# ExtensionBoard.net
KiCad netlist of a schematic drawn in Altium Designer
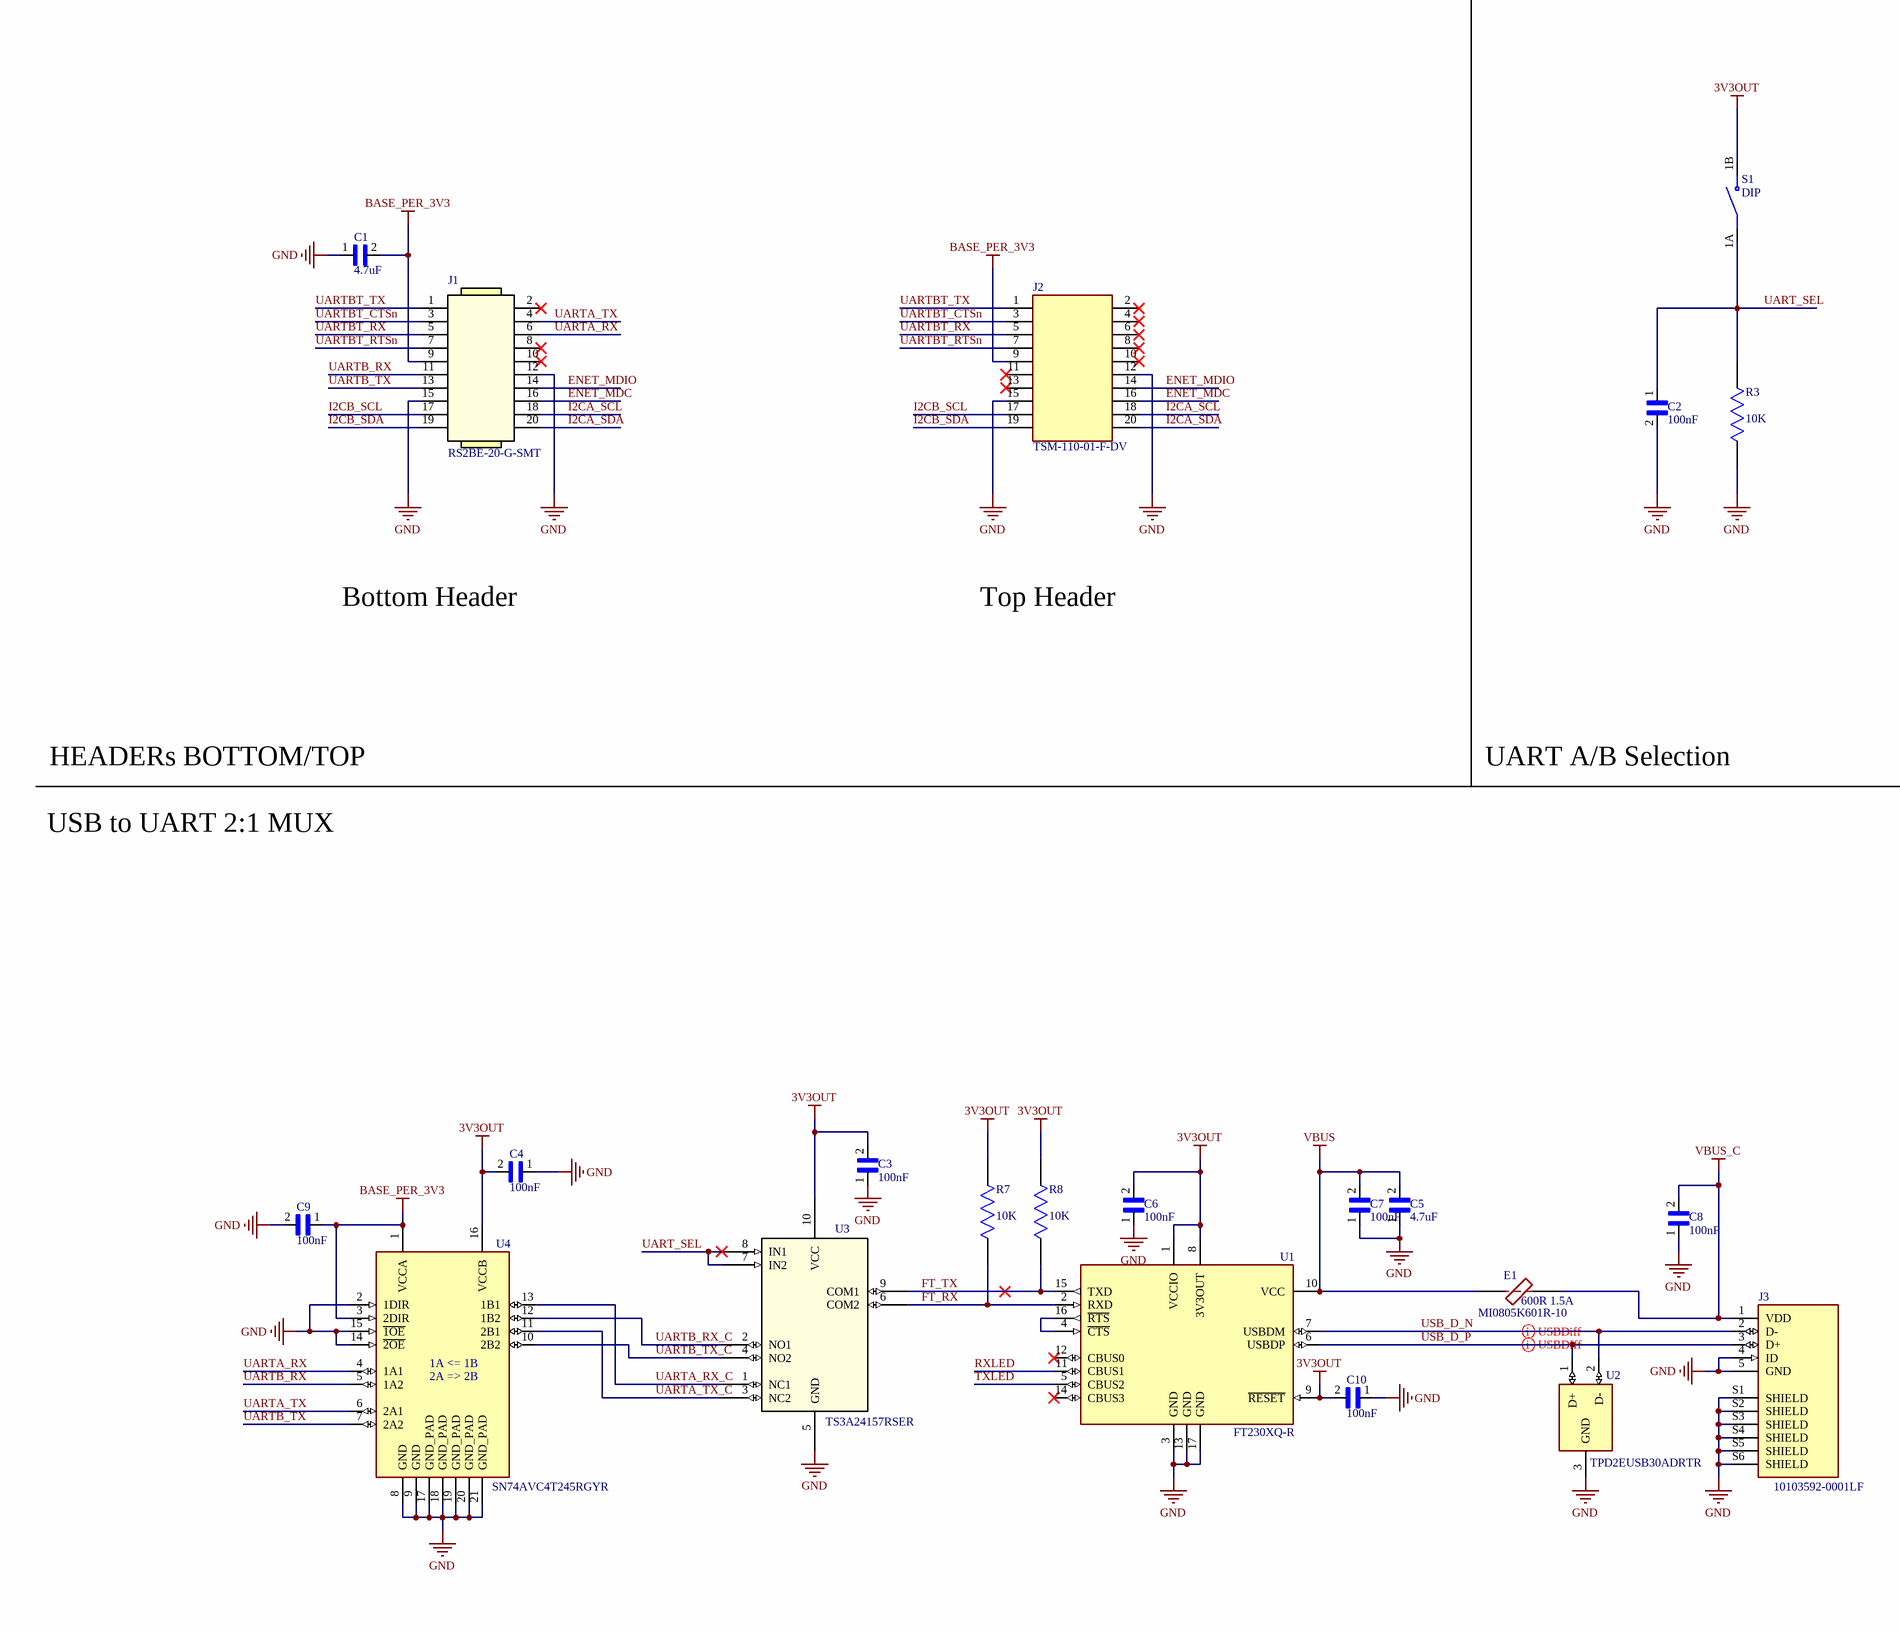
[diagram p0: ExtensionBoard.SchDoc, left]
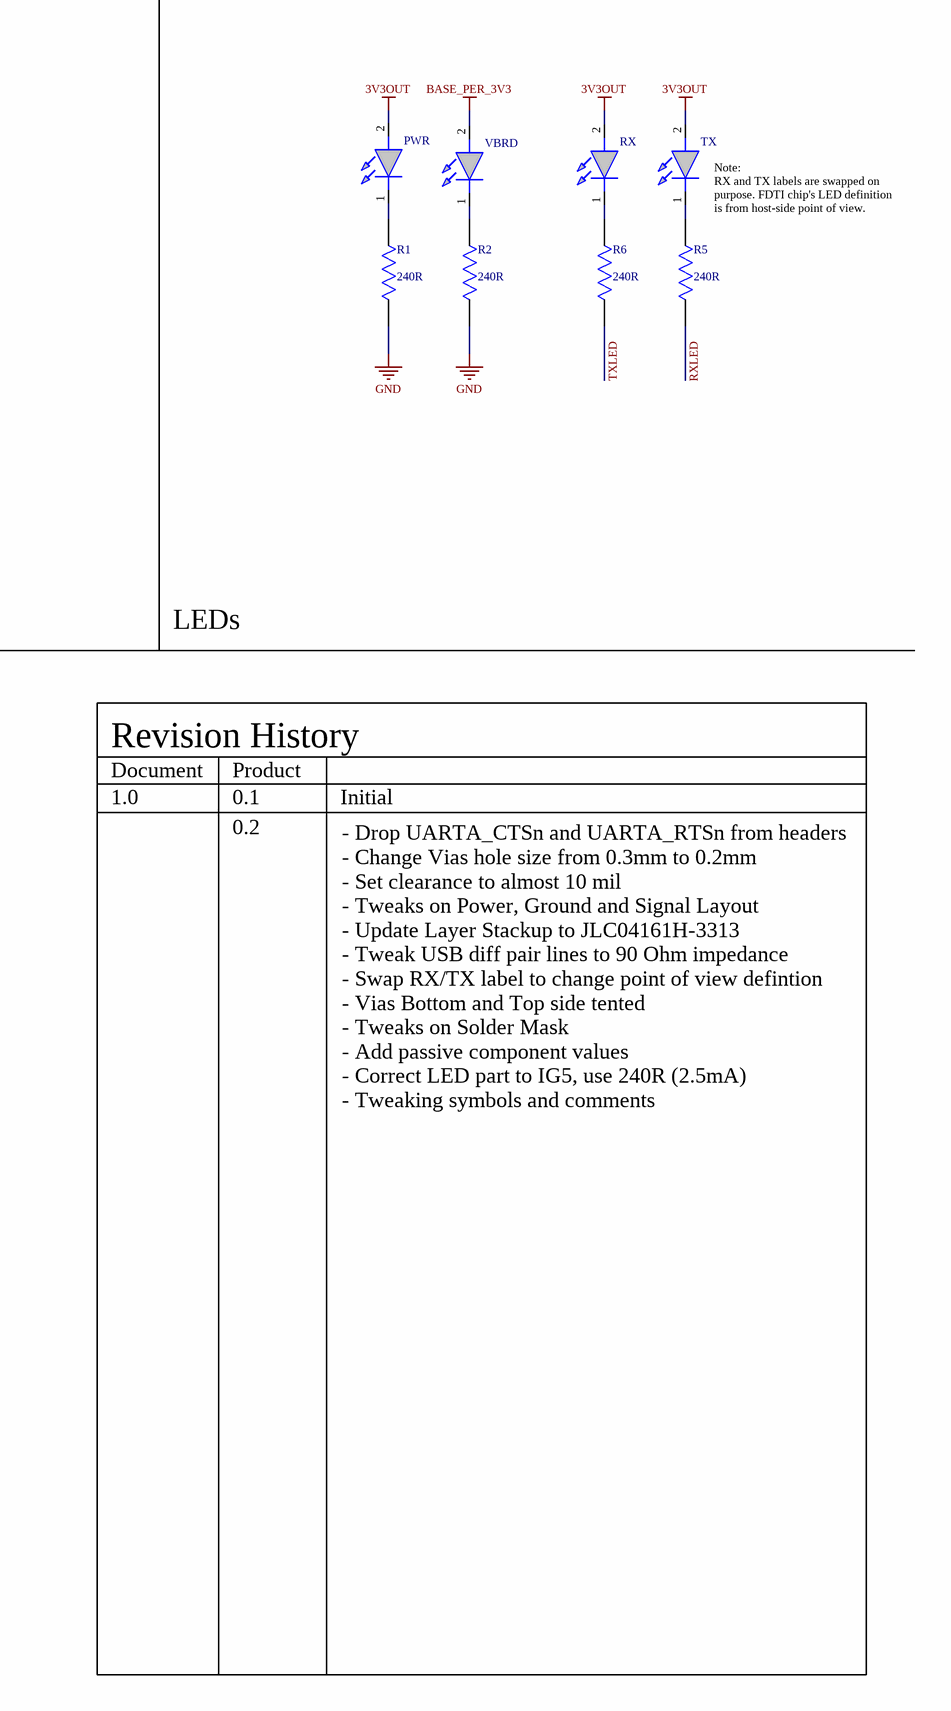
[diagram p1: ExtensionBoard.SchDoc, right]

(export (version "E")
  (design (tool "Eeschema 10.0.6"))
  (components
    (comp (ref "C1")
      (value "4.7uF")
      (footprint "CAPC1608X90N")
      (description "CAPACITOR, MLCC, X5R, 4.7UF, 10V, 0603, REEL, FULL REEL")
      (fields (field (name "MP") "LMK107BJ475KAHT"))
      (libsource (lib "LMK107BJ475KAHT") (part "LMK107BJ475KAHT"))
    )
    (comp (ref "C2")
      (value "100nF")
      (footprint "CAPC1608X90N")
      (description "Cap Ceramic 0.1uF 16V X7R 10% SMD 0603 125ÂÂŽ Paper T/R")
      (fields (field (name "MP") "0603YC104K4T4A"))
      (libsource (lib "0603YC104K4T4A") (part "0603YC104K4T4A"))
    )
    (comp (ref "C3")
      (value "100nF")
      (footprint "CAPC1608X90N")
      (description "Cap Ceramic 0.1uF 16V X7R 10% SMD 0603 125ÂÂŽ Paper T/R")
      (fields (field (name "MP") "0603YC104K4T4A"))
      (libsource (lib "") (part "0603YC104K4T4A_2"))
    )
    (comp (ref "C4")
      (value "100nF")
      (footprint "CAPC1608X90N")
      (description "Cap Ceramic 0.1uF 16V X7R 10% SMD 0603 125ÂÂŽ Paper T/R")
      (fields (field (name "MP") "0603YC104K4T4A"))
      (libsource (lib "") (part "0603YC104K4T4A_1"))
    )
    (comp (ref "C5")
      (value "4.7uF")
      (footprint "CAPC1608X90N")
      (description "CAPACITOR, MLCC, X5R, 4.7UF, 10V, 0603, REEL, FULL REEL")
      (fields (field (name "MP") "LMK107BJ475KAHT"))
      (libsource (lib "") (part "LMK107BJ475KAHT_1"))
    )
    (comp (ref "C6")
      (value "100nF")
      (footprint "CAPC1608X90N")
      (description "Cap Ceramic 0.1uF 16V X7R 10% SMD 0603 125ÂÂŽ Paper T/R")
      (fields (field (name "MP") "0603YC104K4T4A"))
      (libsource (lib "") (part "0603YC104K4T4A_2"))
    )
    (comp (ref "C7")
      (value "100nF")
      (footprint "CAPC1608X90N")
      (description "Cap Ceramic 0.1uF 16V X7R 10% SMD 0603 125ÂÂŽ Paper T/R")
      (fields (field (name "MP") "0603YC104K4T4A"))
      (libsource (lib "") (part "0603YC104K4T4A_2"))
    )
    (comp (ref "C8")
      (value "100nF")
      (footprint "CAPC1608X90N")
      (description "Cap Ceramic 0.1uF 16V X7R 10% SMD 0603 125ÂÂŽ Paper T/R")
      (fields (field (name "MP") "0603YC104K4T4A"))
      (libsource (lib "") (part "0603YC104K4T4A_2"))
    )
    (comp (ref "C9")
      (value "100nF")
      (footprint "CAPC1608X90N")
      (description "Cap Ceramic 0.1uF 16V X7R 10% SMD 0603 125ÂÂŽ Paper T/R")
      (fields (field (name "MP") "0603YC104K4T4A"))
      (libsource (lib "") (part "0603YC104K4T4A_1"))
    )
    (comp (ref "C10")
      (value "100nF")
      (footprint "CAPC1608X90N")
      (description "Cap Ceramic 0.1uF 16V X7R 10% SMD 0603 125ÂÂŽ Paper T/R")
      (fields (field (name "MP") "0603YC104K4T4A"))
      (libsource (lib "") (part "0603YC104K4T4A_1"))
    )
    (comp (ref "E1")
      (value "MI0805K601R-10")
      (footprint "FB_MI0805K601R-10")
      (description "600 Ohms @ 100MHz 1 Power Line Ferrite Bead 0805 (2012 Metric) 1.5A 100mOhm")
      (fields (field (name "ALTIUM_VALUE") "600R 1.5A") (field (name "MF") "Laird-Signal Integrity"))
      (libsource (lib "MI0805K601R-10") (part "MI0805K601R-10"))
    )
    (comp (ref "J1")
      (value "RS2BE-20-G-SMT")
      (footprint "CONN_RS2BE-20-G-SMT_ADM")
      (description "No Description Available")
      (libsource (lib "RS2BE-20-G-SMT") (part "RS2BE-20-G-SMT"))
    )
    (comp (ref "J2")
      (value "TSM-110-01-F-DV")
      (footprint "SAMTEC_TSM-110-01-F-DV")
      (fields (field (name "MF") "Samtec"))
      (libsource (lib "TSM-110-01-F-DV") (part "TSM-110-01-F-DV"))
    )
    (comp (ref "J3")
      (value "10103592-0001LF")
      (footprint "AMPHENOL_10103592-0001LF")
      (description "Micro USB 2.0, Input Output Connectors, B TYPE REVERSE")
      (fields (field (name "MF") "Amphenol ICC") (field (name "DIGI-KEY_PART_NUMBER") "609-4048-2-ND"))
      (libsource (lib "10103592-0001LF") (part "10103592-0001LF"))
    )
    (comp (ref "PWR")
      (value "QBL595-IG5")
      (footprint "LED 0402_1005 GREEN")
      (description "LED Green Clear 0402 SMD")
      (libsource (lib "QBLP595-IG5") (part "QBL595-IG5"))
    )
    (comp (ref "R1")
      (value "240R")
      (footprint "RESC1508X55N")
      (fields (field (name "MP") "RMCF0603JT10K0") (field (name "Comment") "RMCF0603JT240R"))
      (libsource (lib "RMCF0603JT10K0") (part "RMCF0603JT10K0"))
    )
    (comp (ref "R2")
      (value "240R")
      (footprint "RESC1508X55N")
      (fields (field (name "MP") "RMCF0603JT10K0") (field (name "Comment") "RMCF0603JT240R"))
      (libsource (lib "RMCF0603JT10K0") (part "RMCF0603JT10K0"))
    )
    (comp (ref "R3")
      (value "10K")
      (footprint "RESC1508X55N")
      (fields (field (name "MP") "RMCF0603JT10K0"))
      (libsource (lib "RMCF0603JT10K0") (part "RMCF0603JT10K0"))
    )
    (comp (ref "R5")
      (value "240R")
      (footprint "RESC1508X55N")
      (fields (field (name "MP") "RMCF0603JT10K0") (field (name "Comment") "RMCF0603JT240R"))
      (libsource (lib "RMCF0603JT10K0") (part "RMCF0603JT10K0"))
    )
    (comp (ref "R6")
      (value "240R")
      (footprint "RESC1508X55N")
      (fields (field (name "MP") "RMCF0603JT10K0") (field (name "Comment") "RMCF0603JT240R"))
      (libsource (lib "RMCF0603JT10K0") (part "RMCF0603JT10K0"))
    )
    (comp (ref "R7")
      (value "10K")
      (footprint "RESC1508X55N")
      (fields (field (name "MP") "RMCF0603JT10K0"))
      (libsource (lib "RMCF0603JT10K0") (part "RMCF0603JT10K0"))
    )
    (comp (ref "R8")
      (value "10K")
      (footprint "RESC1508X55N")
      (fields (field (name "MP") "RMCF0603JT10K0"))
      (libsource (lib "RMCF0603JT10K0") (part "RMCF0603JT10K0"))
    )
    (comp (ref "RX")
      (value "QBL595-IG5")
      (footprint "LED 0402_1005 GREEN")
      (description "LED Green Clear 0402 SMD")
      (libsource (lib "QBLP595-IG5") (part "QBL595-IG5"))
    )
    (comp (ref "S1")
      (value "DIP")
      (footprint "SW_DS04-254-2-01BK-SMT")
      (description "1 Position, Surface Mount, 2.54 mm Pitch, Flat Slide Actuator, Flat Bottom, SMT Pin, DIP Switch")
      (fields (field (name "MP") "DS04-254-2-01BK-SMT") (field (name "MF") "CUI Devices"))
      (libsource (lib "DS04-254-2-01BK-SMT") (part "DS04-254-2-01BK-SMT"))
    )
    (comp (ref "TX")
      (value "QBL595-IG5")
      (footprint "LED 0402_1005 GREEN")
      (description "LED Green Clear 0402 SMD")
      (libsource (lib "QBLP595-IG5") (part "QBL595-IG5"))
    )
    (comp (ref "U1")
      (value "FT230XQ-R")
      (footprint "FT230XQ-R:QFN65P400X400X80-17N")
      (description "USB Bridge, USB to UART USB 2.0 UART Interface 16-QFN (4x4)")
      (fields (field (name "MF") "FTDI,"))
      (libsource (lib "FT230XQ-R") (part "FT230XQ-R"))
    )
    (comp (ref "U2")
      (value "TPD2EUSB30ADRTR")
      (footprint "SOTFL35P100X50-3N")
      (description "2-Channel ESD/Surge Solution for High-Speed Low-Voltage Interface")
      (fields (field (name "MF") "Texas Instruments"))
      (libsource (lib "TPD2EUSB30ADRTR") (part "TPD2EUSB30ADRTR"))
    )
    (comp (ref "U3")
      (value "TS3A24157RSER")
      (footprint "RSE10")
      (description "No Description Available")
      (libsource (lib "TS3A24157RSER") (part "TS3A24157RSER"))
    )
    (comp (ref "U4")
      (value "SN74AVC4T245RGYR")
      (footprint "QFN50P400X350X100-17N:QFN50P400X350X100-17N")
      (libsource (lib "SN74AVC4T245RGYR") (part "SN74AVC4T245RGYR"))
    )
    (comp (ref "VBRD")
      (value "QBL595-IG5")
      (footprint "LED 0402_1005 GREEN")
      (description "LED Green Clear 0402 SMD")
      (libsource (lib "QBLP595-IG5") (part "QBL595-IG5"))
    )
  )
  (nets
    (net (code "1") (name "/ENET_MDC") (class "Default")
      (node (ref "J1") (pin "16") (pinfunction "16_16") (pintype "passive"))
      (node (ref "J2") (pin "16") (pinfunction "16_16") (pintype "passive"))
    )
    (net (code "2") (name "/ENET_MDIO") (class "Default")
      (node (ref "J1") (pin "14") (pinfunction "14_14") (pintype "passive"))
      (node (ref "J2") (pin "14") (pinfunction "14_14") (pintype "passive"))
    )
    (net (code "3") (name "/FT_RX") (class "Default")
      (node (ref "R7") (pin "1") (pinfunction "1_1") (pintype "passive"))
      (node (ref "U1") (pin "2") (pinfunction "RXD_2") (pintype "input"))
      (node (ref "U3") (pin "6") (pinfunction "COM2_6") (pintype "bidirectional"))
    )
    (net (code "4") (name "/FT_TX") (class "Default")
      (node (ref "R8") (pin "1") (pinfunction "1_1") (pintype "passive"))
      (node (ref "U1") (pin "15") (pinfunction "TXD_15") (pintype "output"))
      (node (ref "U3") (pin "9") (pinfunction "COM1_9") (pintype "bidirectional"))
    )
    (net (code "5") (name "/I2CA_SCL") (class "Default")
      (node (ref "J1") (pin "18") (pinfunction "18_18") (pintype "passive"))
      (node (ref "J2") (pin "18") (pinfunction "18_18") (pintype "passive"))
    )
    (net (code "6") (name "/I2CA_SDA") (class "Default")
      (node (ref "J1") (pin "20") (pinfunction "20_20") (pintype "passive"))
      (node (ref "J2") (pin "20") (pinfunction "20_20") (pintype "passive"))
    )
    (net (code "7") (name "/I2CB_SCL") (class "Default")
      (node (ref "J1") (pin "17") (pinfunction "17_17") (pintype "passive"))
      (node (ref "J2") (pin "17") (pinfunction "17_17") (pintype "passive"))
    )
    (net (code "8") (name "/I2CB_SDA") (class "Default")
      (node (ref "J1") (pin "19") (pinfunction "19_19") (pintype "passive"))
      (node (ref "J2") (pin "19") (pinfunction "19_19") (pintype "passive"))
    )
    (net (code "9") (name "/RXLED") (class "Default")
      (node (ref "R5") (pin "2") (pinfunction "2_2") (pintype "passive"))
      (node (ref "U1") (pin "11") (pinfunction "CBUS1_11") (pintype "bidirectional"))
    )
    (net (code "10") (name "/TXLED") (class "Default")
      (node (ref "R6") (pin "2") (pinfunction "2_2") (pintype "passive"))
      (node (ref "U1") (pin "5") (pinfunction "CBUS2_5") (pintype "bidirectional"))
    )
    (net (code "11") (name "/UARTA_RX") (class "Default")
      (node (ref "J1") (pin "6") (pinfunction "6_6") (pintype "passive"))
      (node (ref "U4") (pin "4") (pinfunction "1A1_4") (pintype "bidirectional"))
    )
    (net (code "12") (name "/UARTA_RX_C") (class "Default")
      (node (ref "U3") (pin "1") (pinfunction "NC1_1") (pintype "bidirectional"))
      (node (ref "U4") (pin "13") (pinfunction "1B1_13") (pintype "bidirectional"))
    )
    (net (code "13") (name "/UARTA_TX") (class "Default")
      (node (ref "J1") (pin "4") (pinfunction "4_4") (pintype "passive"))
      (node (ref "U4") (pin "6") (pinfunction "2A1_6") (pintype "bidirectional"))
    )
    (net (code "14") (name "/UARTA_TX_C") (class "Default")
      (node (ref "U3") (pin "3") (pinfunction "NC2_3") (pintype "bidirectional"))
      (node (ref "U4") (pin "11") (pinfunction "2B1_11") (pintype "bidirectional"))
    )
    (net (code "15") (name "/UARTBT_CTSn") (class "Default")
      (node (ref "J1") (pin "3") (pinfunction "3_3") (pintype "passive"))
      (node (ref "J2") (pin "3") (pinfunction "3_3") (pintype "passive"))
    )
    (net (code "16") (name "/UARTBT_RTSn") (class "Default")
      (node (ref "J1") (pin "7") (pinfunction "7_7") (pintype "passive"))
      (node (ref "J2") (pin "7") (pinfunction "7_7") (pintype "passive"))
    )
    (net (code "17") (name "/UARTBT_RX") (class "Default")
      (node (ref "J1") (pin "5") (pinfunction "5_5") (pintype "passive"))
      (node (ref "J2") (pin "5") (pinfunction "5_5") (pintype "passive"))
    )
    (net (code "18") (name "/UARTBT_TX") (class "Default")
      (node (ref "J1") (pin "1") (pinfunction "1_1") (pintype "passive"))
      (node (ref "J2") (pin "1") (pinfunction "1_1") (pintype "passive"))
    )
    (net (code "19") (name "/UARTB_RX") (class "Default")
      (node (ref "J1") (pin "11") (pinfunction "11_11") (pintype "passive"))
      (node (ref "U4") (pin "5") (pinfunction "1A2_5") (pintype "bidirectional"))
    )
    (net (code "20") (name "/UARTB_RX_C") (class "Default")
      (node (ref "U3") (pin "2") (pinfunction "NO1_2") (pintype "bidirectional"))
      (node (ref "U4") (pin "12") (pinfunction "1B2_12") (pintype "bidirectional"))
    )
    (net (code "21") (name "/UARTB_TX") (class "Default")
      (node (ref "J1") (pin "13") (pinfunction "13_13") (pintype "passive"))
      (node (ref "U4") (pin "7") (pinfunction "2A2_7") (pintype "bidirectional"))
    )
    (net (code "22") (name "/UARTB_TX_C") (class "Default")
      (node (ref "U3") (pin "4") (pinfunction "NO2_4") (pintype "bidirectional"))
      (node (ref "U4") (pin "10") (pinfunction "2B2_10") (pintype "bidirectional"))
    )
    (net (code "23") (name "/UART_SEL") (class "Default")
      (node (ref "C2") (pin "1") (pinfunction "1_1") (pintype "passive"))
      (node (ref "R3") (pin "2") (pinfunction "2_2") (pintype "passive"))
      (node (ref "S1") (pin "1A") (pinfunction "COM_1A") (pintype "passive"))
      (node (ref "U3") (pin "7") (pinfunction "IN2_7") (pintype "input"))
      (node (ref "U3") (pin "8") (pinfunction "IN1_8") (pintype "input"))
    )
    (net (code "24") (name "/USB_D_N") (class "Default")
      (node (ref "J3") (pin "2") (pinfunction "D-_2") (pintype "bidirectional"))
      (node (ref "U1") (pin "7") (pinfunction "USBDM_7") (pintype "bidirectional"))
      (node (ref "U2") (pin "2") (pinfunction "D-_2") (pintype "bidirectional"))
    )
    (net (code "25") (name "/USB_D_P") (class "Default")
      (node (ref "J3") (pin "3") (pinfunction "D+_3") (pintype "bidirectional"))
      (node (ref "U1") (pin "6") (pinfunction "USBDP_6") (pintype "bidirectional"))
      (node (ref "U2") (pin "1") (pinfunction "D+_1") (pintype "bidirectional"))
    )
    (net (code "26") (name "3V3OUT") (class "Default")
      (node (ref "C10") (pin "2") (pinfunction "2_2") (pintype "passive"))
      (node (ref "C3") (pin "2") (pinfunction "2_2") (pintype "passive"))
      (node (ref "C4") (pin "2") (pinfunction "2_2") (pintype "passive"))
      (node (ref "C6") (pin "2") (pinfunction "2_2") (pintype "passive"))
      (node (ref "PWR") (pin "2") (pinfunction "A_2") (pintype "passive"))
      (node (ref "R7") (pin "2") (pinfunction "2_2") (pintype "passive"))
      (node (ref "R8") (pin "2") (pinfunction "2_2") (pintype "passive"))
      (node (ref "RX") (pin "2") (pinfunction "A_2") (pintype "passive"))
      (node (ref "S1") (pin "1B") (pinfunction "NO_1B") (pintype "passive"))
      (node (ref "TX") (pin "2") (pinfunction "A_2") (pintype "passive"))
      (node (ref "U1") (pin "1") (pinfunction "VCCIO_1") (pintype "power_in"))
      (node (ref "U1") (pin "8") (pinfunction "3V3OUT_8") (pintype "power_in"))
      (node (ref "U1") (pin "9") (pinfunction "~{RESET}_9") (pintype "input"))
      (node (ref "U3") (pin "10") (pinfunction "VCC_10") (pintype "power_in"))
      (node (ref "U4") (pin "16") (pinfunction "VCCB_16") (pintype "power_in"))
    )
    (net (code "27") (name "BASE_PER_3V3") (class "Default")
      (node (ref "C1") (pin "2") (pinfunction "2_2") (pintype "passive"))
      (node (ref "C9") (pin "1") (pinfunction "1_1") (pintype "passive"))
      (node (ref "J1") (pin "9") (pinfunction "9_9") (pintype "passive"))
      (node (ref "J2") (pin "9") (pinfunction "9_9") (pintype "passive"))
      (node (ref "U4") (pin "1") (pinfunction "VCCA_1") (pintype "power_in"))
      (node (ref "U4") (pin "3") (pinfunction "2DIR_3") (pintype "input"))
      (node (ref "VBRD") (pin "2") (pinfunction "A_2") (pintype "passive"))
    )
    (net (code "28") (name "GND") (class "Default")
      (node (ref "C1") (pin "1") (pinfunction "1_1") (pintype "passive"))
      (node (ref "C10") (pin "1") (pinfunction "1_1") (pintype "passive"))
      (node (ref "C2") (pin "2") (pinfunction "2_2") (pintype "passive"))
      (node (ref "C3") (pin "1") (pinfunction "1_1") (pintype "passive"))
      (node (ref "C4") (pin "1") (pinfunction "1_1") (pintype "passive"))
      (node (ref "C5") (pin "1") (pinfunction "1_1") (pintype "passive"))
      (node (ref "C6") (pin "1") (pinfunction "1_1") (pintype "passive"))
      (node (ref "C7") (pin "1") (pinfunction "1_1") (pintype "passive"))
      (node (ref "C8") (pin "1") (pinfunction "1_1") (pintype "passive"))
      (node (ref "C9") (pin "2") (pinfunction "2_2") (pintype "passive"))
      (node (ref "J1") (pin "12") (pinfunction "12_12") (pintype "passive"))
      (node (ref "J1") (pin "15") (pinfunction "15_15") (pintype "passive"))
      (node (ref "J2") (pin "12") (pinfunction "12_12") (pintype "passive"))
      (node (ref "J2") (pin "15") (pinfunction "15_15") (pintype "passive"))
      (node (ref "J3") (pin "4") (pinfunction "ID_4") (pintype "input"))
      (node (ref "J3") (pin "5") (pinfunction "GND_5") (pintype "power_in"))
      (node (ref "J3") (pin "S1") (pinfunction "SHIELD_S1") (pintype "power_in"))
      (node (ref "J3") (pin "S2") (pinfunction "SHIELD_S2") (pintype "power_in"))
      (node (ref "J3") (pin "S3") (pinfunction "SHIELD_S3") (pintype "power_in"))
      (node (ref "J3") (pin "S4") (pinfunction "SHIELD_S4") (pintype "power_in"))
      (node (ref "J3") (pin "S5") (pinfunction "SHIELD_S5") (pintype "power_in"))
      (node (ref "J3") (pin "S6") (pinfunction "SHIELD_S6") (pintype "power_in"))
      (node (ref "R1") (pin "1") (pinfunction "1_1") (pintype "passive"))
      (node (ref "R2") (pin "1") (pinfunction "1_1") (pintype "passive"))
      (node (ref "R3") (pin "1") (pinfunction "1_1") (pintype "passive"))
      (node (ref "U1") (pin "13") (pinfunction "GND_13") (pintype "power_in"))
      (node (ref "U1") (pin "17") (pinfunction "GND_17") (pintype "power_in"))
      (node (ref "U1") (pin "3") (pinfunction "GND_3") (pintype "power_in"))
      (node (ref "U2") (pin "3") (pinfunction "GND_3") (pintype "power_in"))
      (node (ref "U3") (pin "5") (pinfunction "GND_5") (pintype "power_in"))
      (node (ref "U4") (pin "14") (pinfunction "~{2OE}_14") (pintype "input"))
      (node (ref "U4") (pin "15") (pinfunction "~{1OE}_15") (pintype "input"))
      (node (ref "U4") (pin "17") (pinfunction "GND_PAD_17") (pintype "power_in"))
      (node (ref "U4") (pin "18") (pinfunction "GND_PAD_18") (pintype "power_in"))
      (node (ref "U4") (pin "19") (pinfunction "GND_PAD_19") (pintype "power_in"))
      (node (ref "U4") (pin "2") (pinfunction "1DIR_2") (pintype "input"))
      (node (ref "U4") (pin "20") (pinfunction "GND_PAD_20") (pintype "power_in"))
      (node (ref "U4") (pin "21") (pinfunction "GND_PAD_21") (pintype "power_in"))
      (node (ref "U4") (pin "8") (pinfunction "GND_8") (pintype "power_in"))
      (node (ref "U4") (pin "9") (pinfunction "GND_9") (pintype "power_in"))
    )
    (net (code "29") (name "Net-(PWR-K)") (class "Default")
      (node (ref "PWR") (pin "1") (pinfunction "K_1") (pintype "passive"))
      (node (ref "R1") (pin "2") (pinfunction "2_2") (pintype "passive"))
    )
    (net (code "30") (name "Net-(RX-K)") (class "Default")
      (node (ref "R6") (pin "1") (pinfunction "1_1") (pintype "passive"))
      (node (ref "RX") (pin "1") (pinfunction "K_1") (pintype "passive"))
    )
    (net (code "31") (name "Net-(TX-K)") (class "Default")
      (node (ref "R5") (pin "1") (pinfunction "1_1") (pintype "passive"))
      (node (ref "TX") (pin "1") (pinfunction "K_1") (pintype "passive"))
    )
    (net (code "32") (name "Net-(U1-~{CTS})") (class "Default")
      (node (ref "U1") (pin "16") (pinfunction "~{RTS}_16") (pintype "output"))
      (node (ref "U1") (pin "4") (pinfunction "~{CTS}_4") (pintype "input"))
    )
    (net (code "33") (name "Net-(VBRD-K)") (class "Default")
      (node (ref "R2") (pin "2") (pinfunction "2_2") (pintype "passive"))
      (node (ref "VBRD") (pin "1") (pinfunction "K_1") (pintype "passive"))
    )
    (net (code "34") (name "VBUS") (class "Default")
      (node (ref "C5") (pin "2") (pinfunction "2_2") (pintype "passive"))
      (node (ref "C7") (pin "2") (pinfunction "2_2") (pintype "passive"))
      (node (ref "E1") (pin "1") (pinfunction "1_1") (pintype "passive"))
      (node (ref "U1") (pin "10") (pinfunction "VCC_10") (pintype "power_in"))
    )
    (net (code "35") (name "VBUS_C") (class "Default")
      (node (ref "C8") (pin "2") (pinfunction "2_2") (pintype "passive"))
      (node (ref "E1") (pin "2") (pinfunction "2_2") (pintype "passive"))
      (node (ref "J3") (pin "1") (pinfunction "VDD_1") (pintype "power_in"))
    )
    (net (code "36") (name "unconnected-(J1-Pad2)") (class "Default")
      (node (ref "J1") (pin "2") (pinfunction "2_2") (pintype "passive+no_connect"))
    )
    (net (code "37") (name "unconnected-(J1-Pad8)") (class "Default")
      (node (ref "J1") (pin "8") (pinfunction "8_8") (pintype "passive+no_connect"))
    )
    (net (code "38") (name "unconnected-(J1-Pad10)") (class "Default")
      (node (ref "J1") (pin "10") (pinfunction "10_10") (pintype "passive+no_connect"))
    )
    (net (code "39") (name "unconnected-(J2-Pad2)") (class "Default")
      (node (ref "J2") (pin "2") (pinfunction "2_2") (pintype "passive+no_connect"))
    )
    (net (code "40") (name "unconnected-(J2-Pad4)") (class "Default")
      (node (ref "J2") (pin "4") (pinfunction "4_4") (pintype "passive+no_connect"))
    )
    (net (code "41") (name "unconnected-(J2-Pad6)") (class "Default")
      (node (ref "J2") (pin "6") (pinfunction "6_6") (pintype "passive+no_connect"))
    )
    (net (code "42") (name "unconnected-(J2-Pad8)") (class "Default")
      (node (ref "J2") (pin "8") (pinfunction "8_8") (pintype "passive+no_connect"))
    )
    (net (code "43") (name "unconnected-(J2-Pad10)") (class "Default")
      (node (ref "J2") (pin "10") (pinfunction "10_10") (pintype "passive+no_connect"))
    )
    (net (code "44") (name "unconnected-(J2-Pad11)") (class "Default")
      (node (ref "J2") (pin "11") (pinfunction "11_11") (pintype "passive+no_connect"))
    )
    (net (code "45") (name "unconnected-(J2-Pad13)") (class "Default")
      (node (ref "J2") (pin "13") (pinfunction "13_13") (pintype "passive+no_connect"))
    )
    (net (code "46") (name "unconnected-(U1-CBUS0-Pad12)") (class "Default")
      (node (ref "U1") (pin "12") (pinfunction "CBUS0_12") (pintype "bidirectional+no_connect"))
    )
    (net (code "47") (name "unconnected-(U1-CBUS3-Pad14)") (class "Default")
      (node (ref "U1") (pin "14") (pinfunction "CBUS3_14") (pintype "bidirectional+no_connect"))
    )
  )
)
